# LCEDA_schematic_esp_trans_v2.net
KiCad netlist of a schematic drawn in EasyEDA
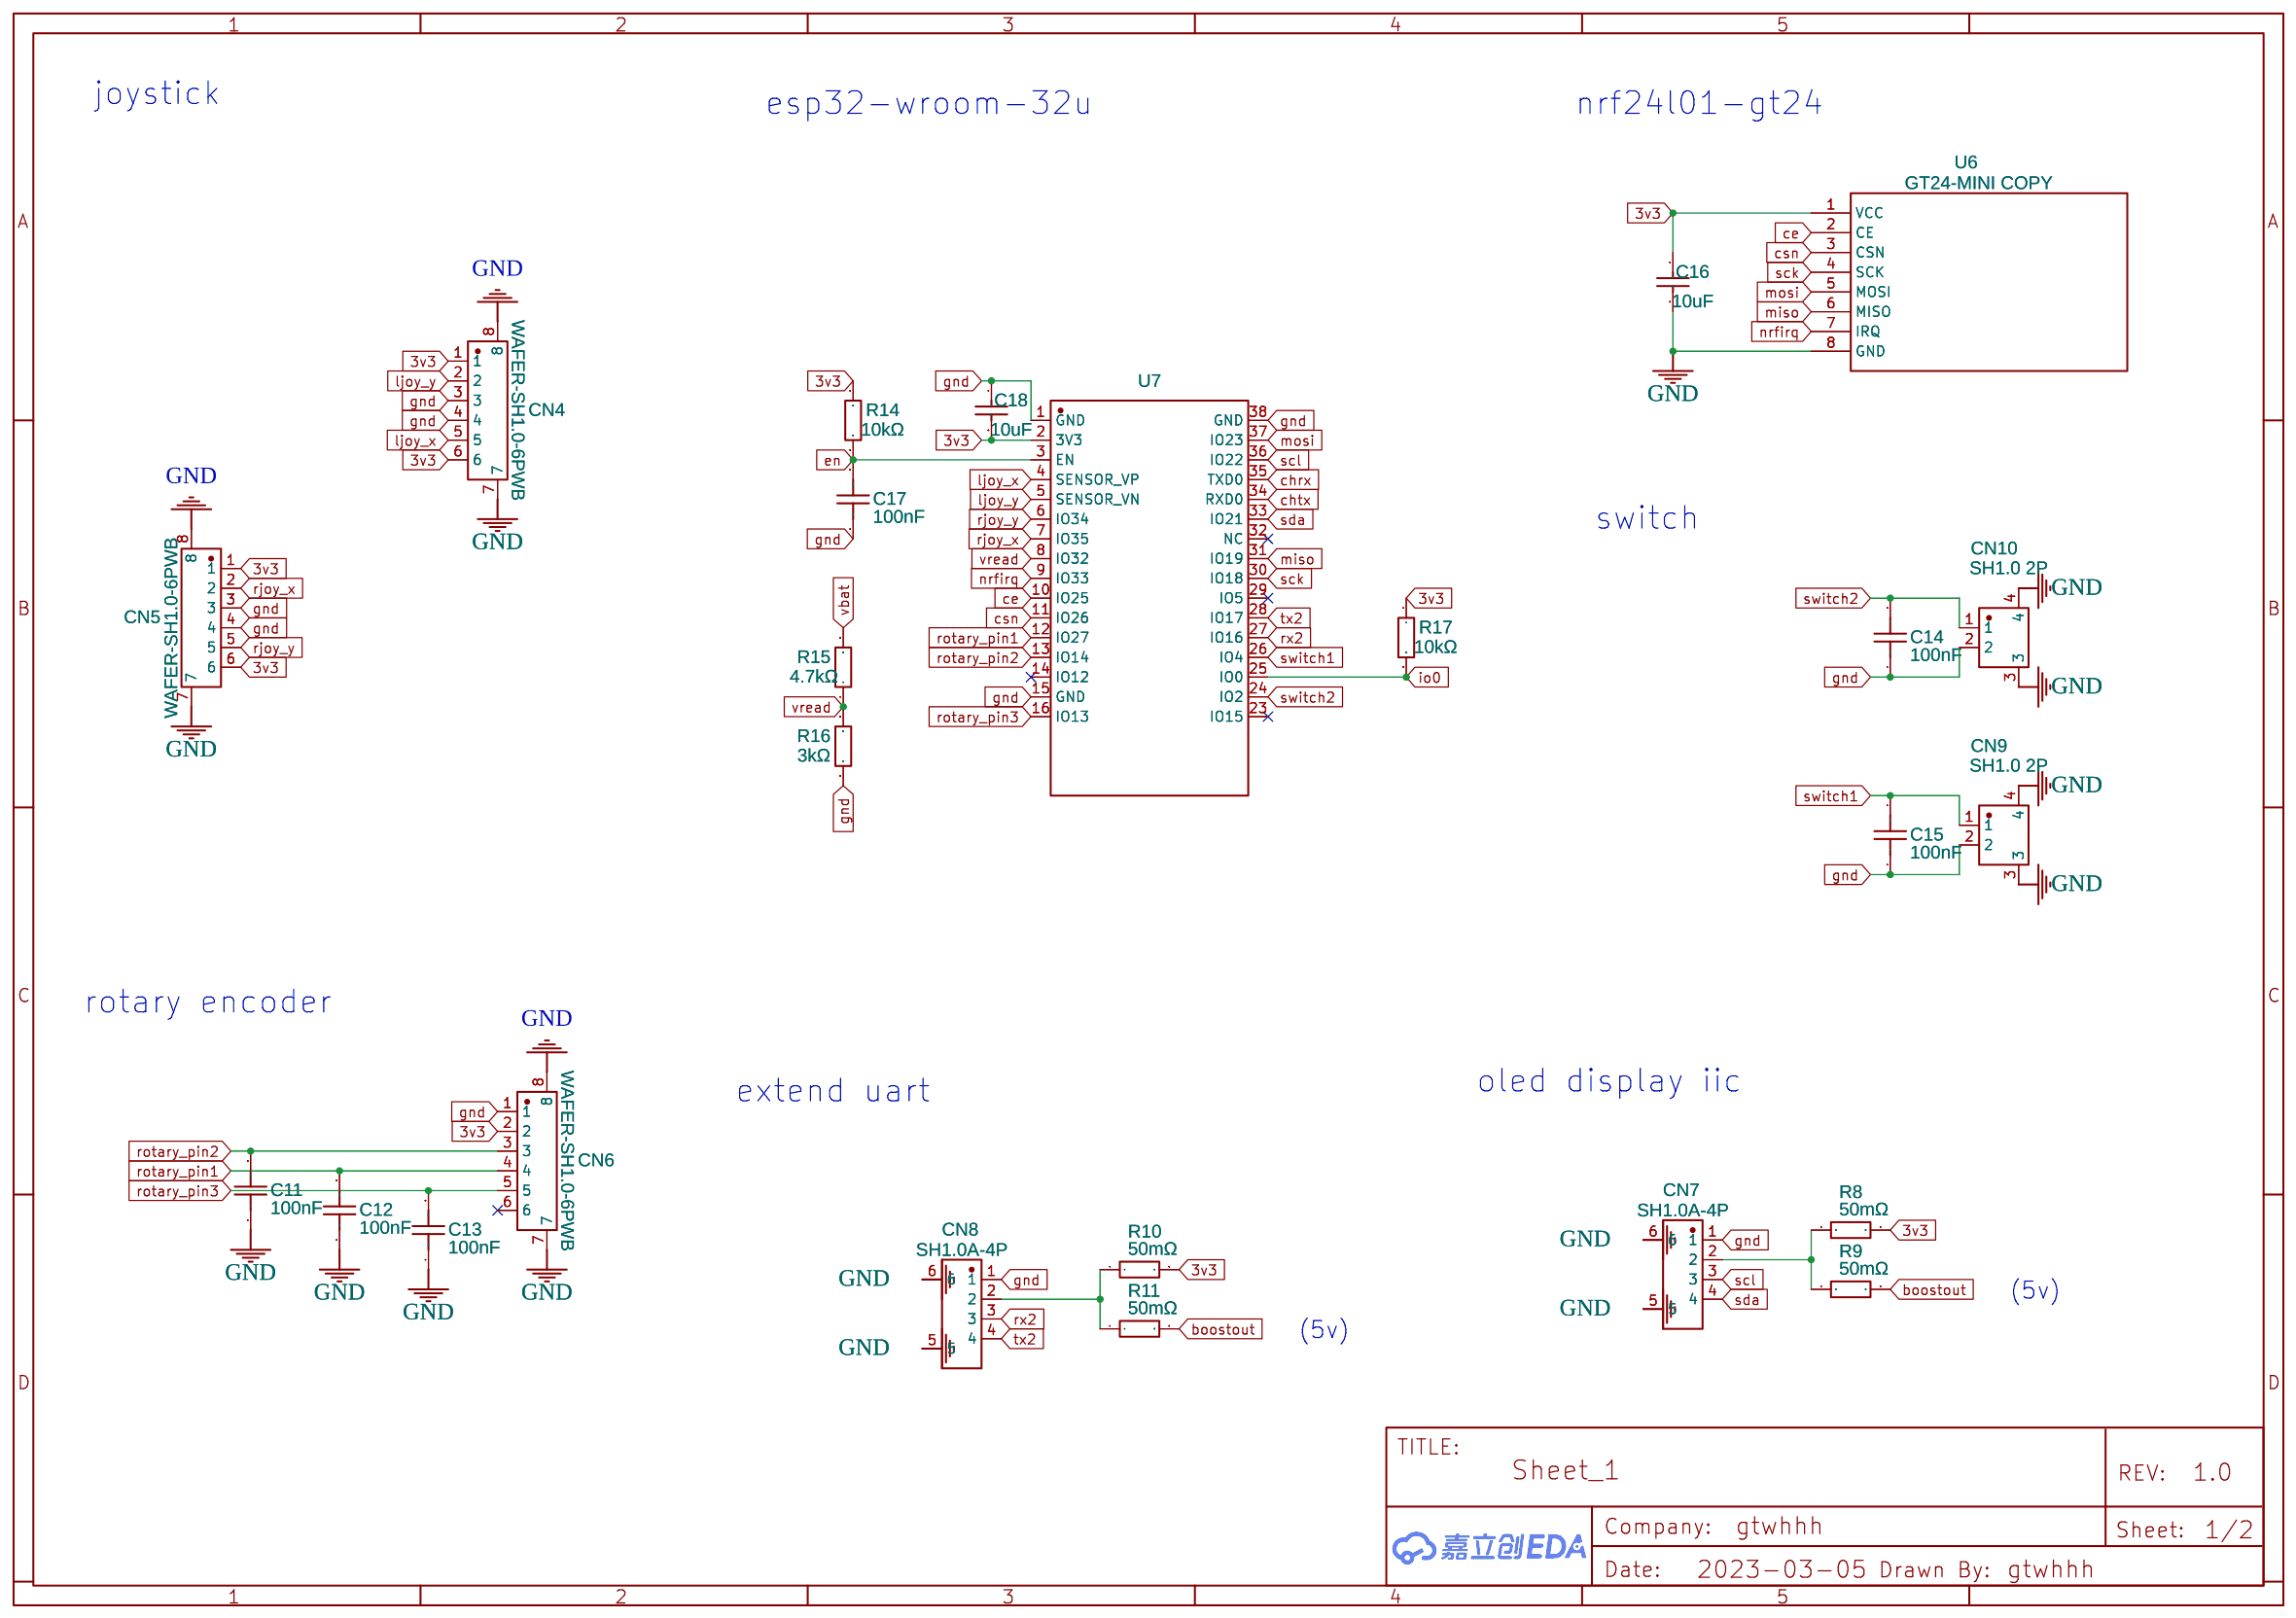
[diagram p0: Sheet_1]
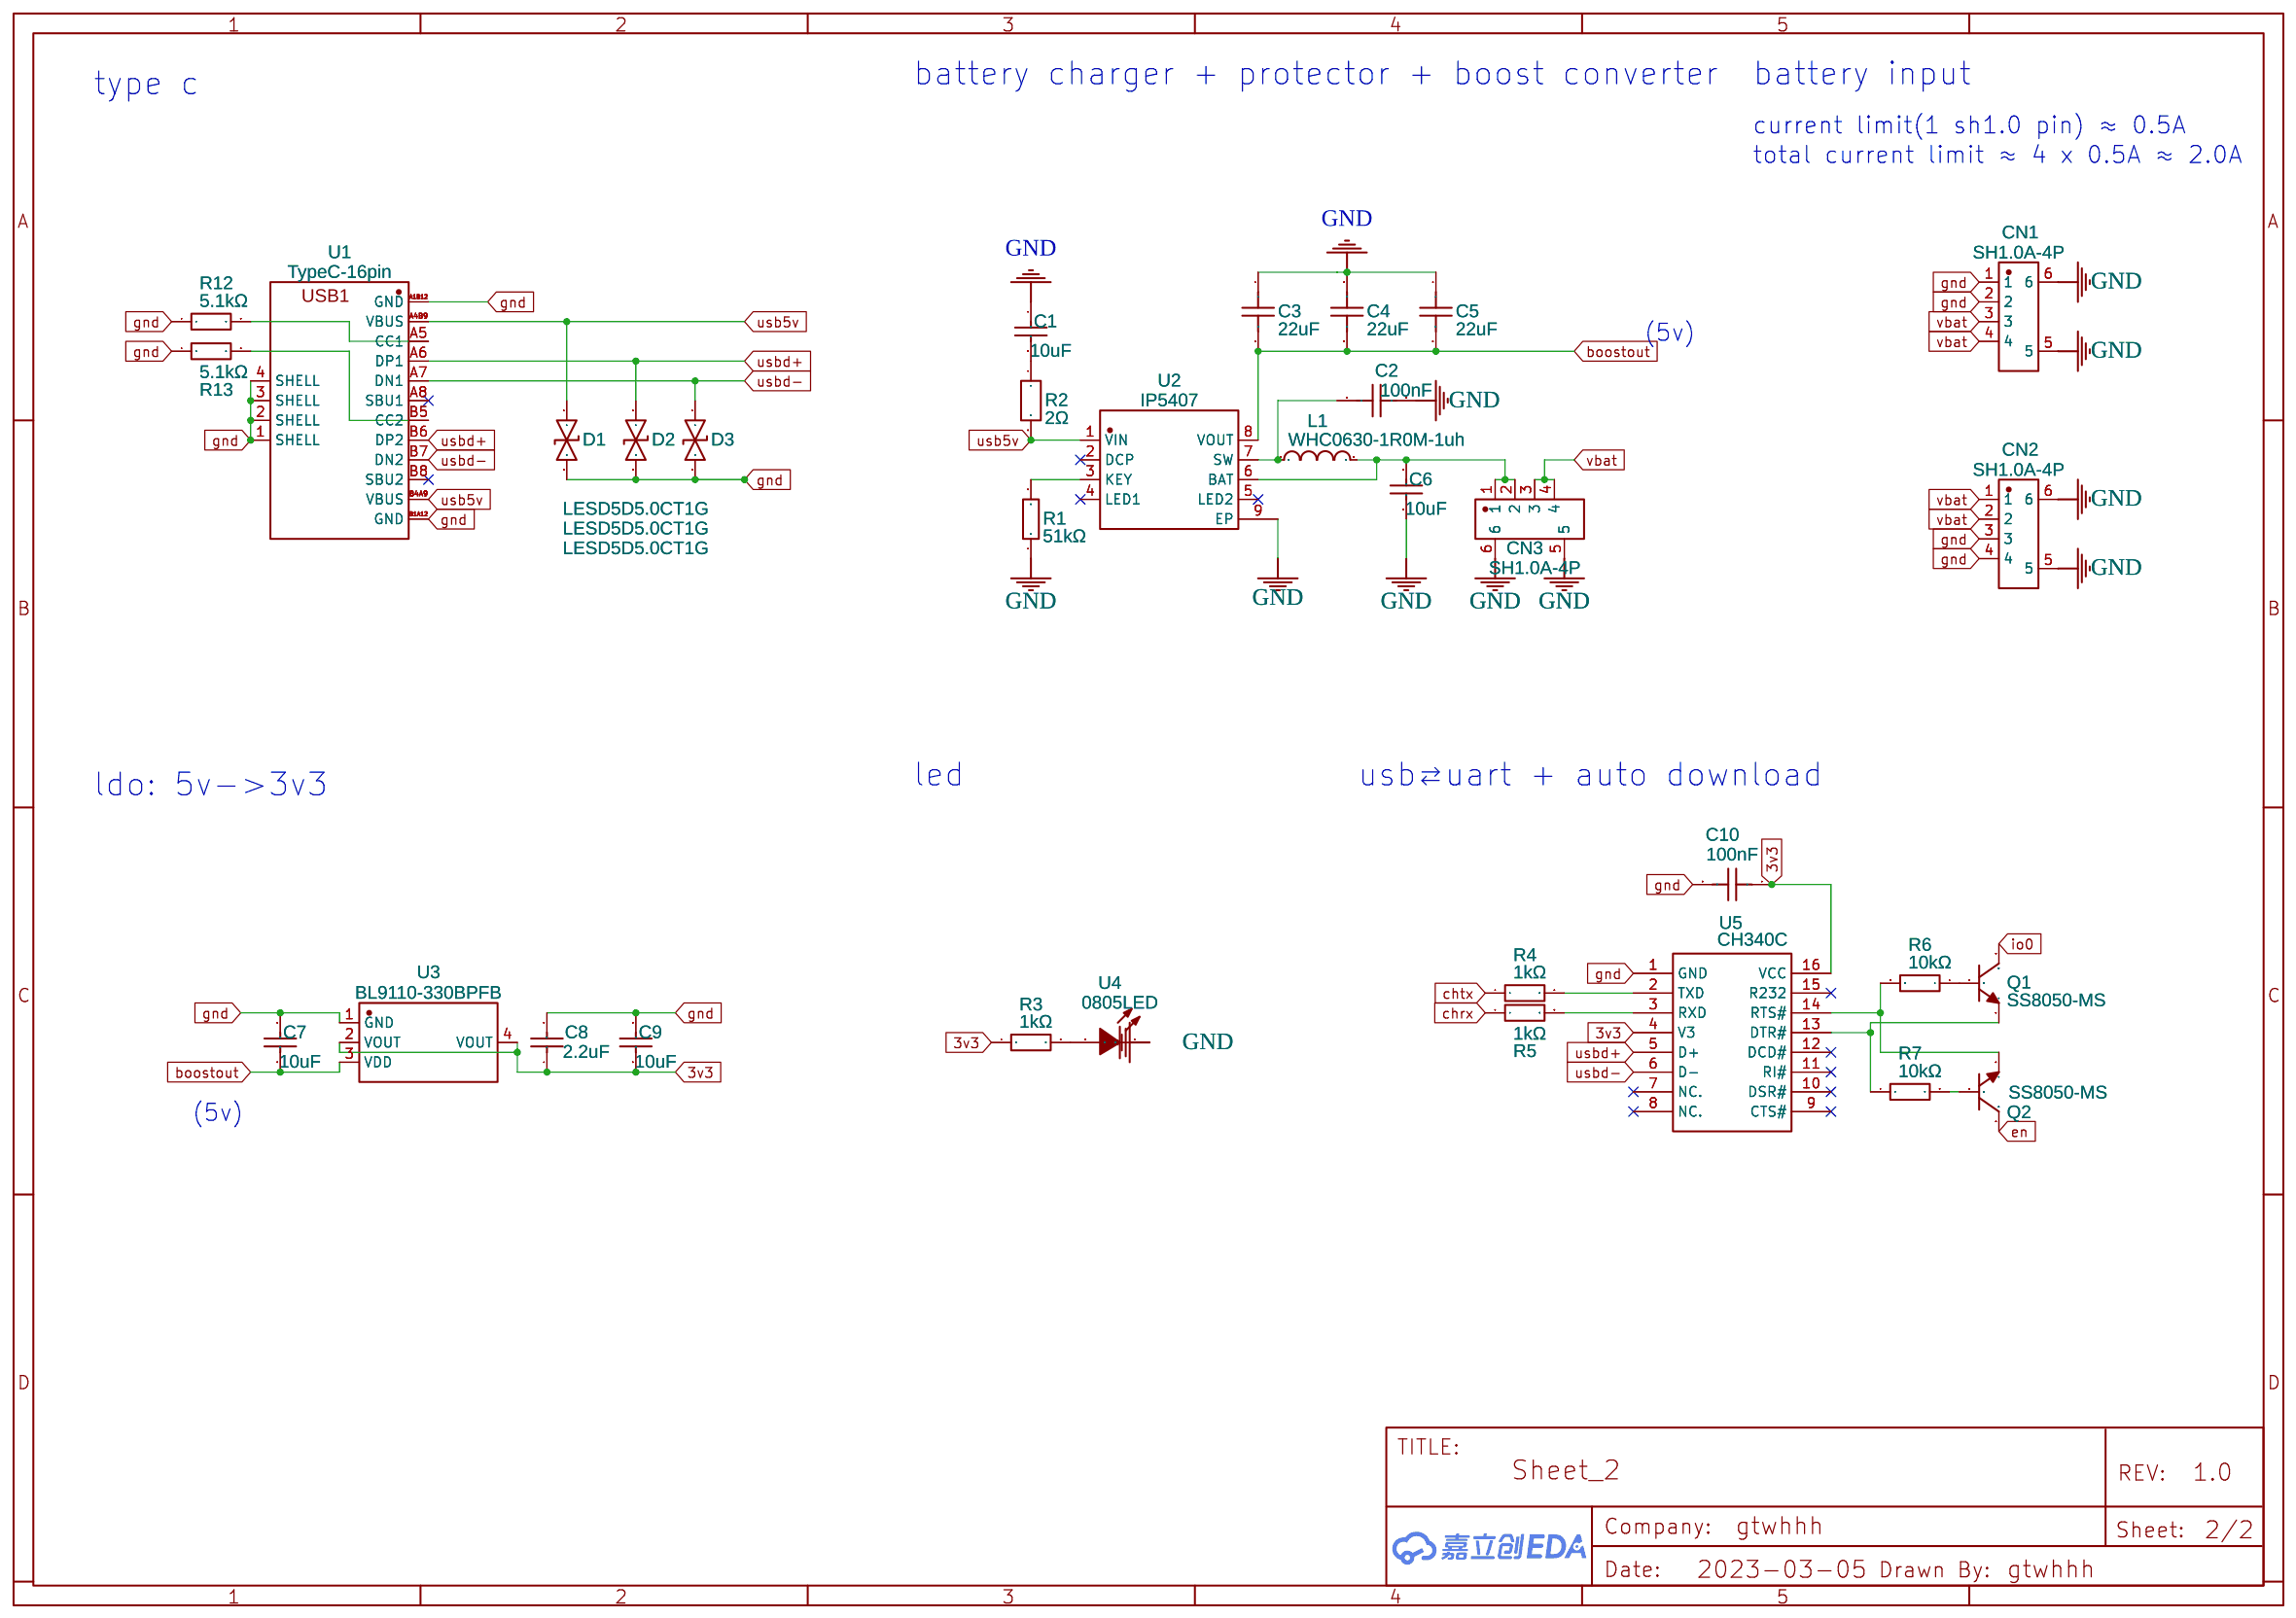
[diagram p1: Sheet_2]

(export (version "E")
  (design (tool "Eeschema 10.0.6"))
  (components
    (comp (ref "C11")
      (value "100nF")
      (fields (field (name "Manufacturer Part") "0805B104K500CT") (field (name "Manufacturer") "Walsin(华新科)"))
      (libsource (lib "") (part "0805B104K500"))
    )
    (comp (ref "C12")
      (value "100nF")
      (fields (field (name "Manufacturer Part") "0805B104K500CT") (field (name "Manufacturer") "Walsin(华新科)"))
      (libsource (lib "") (part "0805B104K500"))
    )
    (comp (ref "C13")
      (value "100nF")
      (fields (field (name "Manufacturer Part") "0805B104K500CT") (field (name "Manufacturer") "Walsin(华新科)"))
      (libsource (lib "") (part "0805B104K500"))
    )
    (comp (ref "C14")
      (value "100nF")
      (fields (field (name "Manufacturer Part") "0805B104K500CT") (field (name "Manufacturer") "Walsin(华新科)"))
      (libsource (lib "") (part "0805B104K500"))
    )
    (comp (ref "C15")
      (value "100nF")
      (fields (field (name "Manufacturer Part") "0805B104K500CT") (field (name "Manufacturer") "Walsin(华新科)"))
      (libsource (lib "") (part "0805B104K500"))
    )
    (comp (ref "C16")
      (value "10uF")
      (fields (field (name "Manufacturer Part") "0805X106K250NT") (field (name "Manufacturer") "FH(风华)"))
      (libsource (lib "") (part "0805X106K250NT"))
    )
    (comp (ref "C17")
      (value "100nF")
      (fields (field (name "Manufacturer Part") "0805B104K500CT") (field (name "Manufacturer") "Walsin(华新科)"))
      (libsource (lib "") (part "0805B104K500"))
    )
    (comp (ref "C18")
      (value "10uF")
      (fields (field (name "Manufacturer Part") "0805X106K250NT") (field (name "Manufacturer") "FH(风华)"))
      (libsource (lib "") (part "0805X106K250NT"))
    )
    (comp (ref "CN4")
      (value "WAFER-SH1.0-6PWB")
      (fields (field (name "Manufacturer") "XUNPU(讯普)"))
      (libsource (lib "") (part "WAFER-SH1.0-6PWB"))
    )
    (comp (ref "CN5")
      (value "WAFER-SH1.0-6PWB")
      (fields (field (name "Manufacturer") "XUNPU(讯普)"))
      (libsource (lib "") (part "WAFER-SH1.0-6PWB_1"))
    )
    (comp (ref "CN6")
      (value "WAFER-SH1.0-6PWB")
      (fields (field (name "Manufacturer") "XUNPU(讯普)"))
      (libsource (lib "") (part "WAFER-SH1.0-6PWB"))
    )
    (comp (ref "CN7")
      (value "SH1.0A-4P")
      (fields (field (name "Manufacturer Part") "SH1.0A-4P 卧贴"))
      (libsource (lib "") (part "SH1.0A-4P 卧贴"))
    )
    (comp (ref "CN8")
      (value "SH1.0A-4P")
      (fields (field (name "Manufacturer Part") "SH1.0A-4P 卧贴"))
      (libsource (lib "") (part "SH1.0A-4P 卧贴"))
    )
    (comp (ref "CN9")
      (value "SH1.0 2P")
      (fields (field (name "Manufacturer Part") "WAFER-SH1.0-2PWB") (field (name "Manufacturer") "XUNPU(讯普)"))
      (libsource (lib "") (part "EPHB_WAFER-SH1.0-2PWB COPY1 SH1.0 2P 卧贴"))
    )
    (comp (ref "CN10")
      (value "SH1.0 2P")
      (fields (field (name "Manufacturer Part") "WAFER-SH1.0-2PWB") (field (name "Manufacturer") "XUNPU(讯普)"))
      (libsource (lib "") (part "EPHB_WAFER-SH1.0-2PWB COPY1 SH1.0 2P 卧贴"))
    )
    (comp (ref "R8")
      (value "50mΩ")
      (fields (field (name "Manufacturer Part") "RL0805FR-070R05L") (field (name "Manufacturer") "YAGEO(国巨)"))
      (libsource (lib "") (part "RL0805FR-070R05L"))
    )
    (comp (ref "R9")
      (value "50mΩ")
      (fields (field (name "Manufacturer Part") "RL0805FR-070R05L") (field (name "Manufacturer") "YAGEO(国巨)"))
      (libsource (lib "") (part "RL0805FR-070R05L"))
    )
    (comp (ref "R10")
      (value "50mΩ")
      (fields (field (name "Manufacturer Part") "RL0805FR-070R05L") (field (name "Manufacturer") "YAGEO(国巨)"))
      (libsource (lib "") (part "RL0805FR-070R05L"))
    )
    (comp (ref "R11")
      (value "50mΩ")
      (fields (field (name "Manufacturer Part") "RL0805FR-070R05L") (field (name "Manufacturer") "YAGEO(国巨)"))
      (libsource (lib "") (part "RL0805FR-070R05L"))
    )
    (comp (ref "R14")
      (value "10kΩ")
      (fields (field (name "Manufacturer Part") "AC0805FR-0710KL") (field (name "Manufacturer") "YAGEO(国巨)"))
      (libsource (lib "") (part "AC0805FR-0710KL"))
    )
    (comp (ref "R15")
      (value "4.7kΩ")
      (fields (field (name "Manufacturer Part") "RC0805JR-074K7L") (field (name "Manufacturer") "YAGEO(国巨)"))
      (libsource (lib "") (part "RC0805JR-074K7L"))
    )
    (comp (ref "R16")
      (value "3kΩ")
      (fields (field (name "Manufacturer Part") "RC0805FR-073KL") (field (name "Manufacturer") "YAGEO(国巨)"))
      (libsource (lib "") (part "RC0805FR-073KL"))
    )
    (comp (ref "R17")
      (value "10kΩ")
      (fields (field (name "Manufacturer Part") "AC0805FR-0710KL") (field (name "Manufacturer") "YAGEO(国巨)"))
      (libsource (lib "") (part "AC0805FR-0710KL"))
    )
    (comp (ref "U6") (value "GT24-MINI COPY") (libsource (lib "") (part "GT24-MINI COPY")))
    (comp (ref "U7")
      (value "NO")
      (fields (field (name "Manufacturer Part") "123"))
      (libsource (lib "") (part "esp3232"))
    )
    (comp (ref "C1")
      (value "10uF")
      (fields (field (name "Manufacturer Part") "0805X106K250NT") (field (name "Manufacturer") "FH(风华)"))
      (libsource (lib "") (part "0805X106K250NT"))
    )
    (comp (ref "C2")
      (value "100nF")
      (fields (field (name "Manufacturer Part") "0805B104K500CT") (field (name "Manufacturer") "Walsin(华新科)"))
      (libsource (lib "") (part "0805B104K500"))
    )
    (comp (ref "C3")
      (value "22uF")
      (fields (field (name "Manufacturer Part") "0805X226M160NT") (field (name "Manufacturer") "FH(风华)"))
      (libsource (lib "") (part "0805X226M160NT"))
    )
    (comp (ref "C4")
      (value "22uF")
      (fields (field (name "Manufacturer Part") "0805X226M160NT") (field (name "Manufacturer") "FH(风华)"))
      (libsource (lib "") (part "0805X226M160NT"))
    )
    (comp (ref "C5")
      (value "22uF")
      (fields (field (name "Manufacturer Part") "0805X226M160NT") (field (name "Manufacturer") "FH(风华)"))
      (libsource (lib "") (part "0805X226M160NT"))
    )
    (comp (ref "C6")
      (value "10uF")
      (fields (field (name "Manufacturer Part") "0805X106K250NT") (field (name "Manufacturer") "FH(风华)"))
      (libsource (lib "") (part "0805X106K250NT"))
    )
    (comp (ref "C7")
      (value "10uF")
      (fields (field (name "Manufacturer Part") "0805X106K250NT") (field (name "Manufacturer") "FH(风华)"))
      (libsource (lib "") (part "0805X106K250NT"))
    )
    (comp (ref "C8")
      (value "2.2uF")
      (fields (field (name "Manufacturer Part") "0805B225K250NT") (field (name "Manufacturer") "FH(风华)"))
      (libsource (lib "") (part "0805B225K250NT"))
    )
    (comp (ref "C9")
      (value "10uF")
      (fields (field (name "Manufacturer Part") "0805X106K250NT") (field (name "Manufacturer") "FH(风华)"))
      (libsource (lib "") (part "0805X106K250NT"))
    )
    (comp (ref "C10")
      (value "100nF")
      (fields (field (name "Manufacturer Part") "0805B104K500CT") (field (name "Manufacturer") "Walsin(华新科)"))
      (libsource (lib "") (part "0805B104K500"))
    )
    (comp (ref "CN1")
      (value "SH1.0A-4P")
      (fields (field (name "Manufacturer Part") "SH1.0A-4P 卧贴"))
      (libsource (lib "") (part "SH1.0A-4P 卧贴_1"))
    )
    (comp (ref "CN2")
      (value "SH1.0A-4P")
      (fields (field (name "Manufacturer Part") "SH1.0A-4P 卧贴"))
      (libsource (lib "") (part "SH1.0A-4P 卧贴_1"))
    )
    (comp (ref "CN3")
      (value "SH1.0A-4P")
      (fields (field (name "Manufacturer Part") "SH1.0A-4P 卧贴"))
      (libsource (lib "") (part "SH1.0A-4P 卧贴"))
    )
    (comp (ref "D1")
      (value "LESD5D5.0CT1G")
      (fields (field (name "Manufacturer") "LRC(乐山无线电)"))
      (libsource (lib "") (part "LESD5D5.0CT1G"))
    )
    (comp (ref "D2")
      (value "LESD5D5.0CT1G")
      (fields (field (name "Manufacturer") "LRC(乐山无线电)"))
      (libsource (lib "") (part "LESD5D5.0CT1G"))
    )
    (comp (ref "D3")
      (value "LESD5D5.0CT1G")
      (fields (field (name "Manufacturer") "LRC(乐山无线电)"))
      (libsource (lib "") (part "LESD5D5.0CT1G"))
    )
    (comp (ref "L1")
      (value "WHC0630-1R0M-1uh")
      (fields (field (name "Manufacturer Part") "MPCA-0630-1R0-M") (field (name "Manufacturer") "MAZO"))
      (libsource (lib "") (part "0630-1R0电感"))
    )
    (comp (ref "Q1")
      (value "SS8050-MS")
      (fields (field (name "Manufacturer") "MSKSEMI(美森科)"))
      (libsource (lib "") (part "SS8050-MS_1"))
    )
    (comp (ref "Q2")
      (value "SS8050-MS")
      (fields (field (name "Manufacturer") "MSKSEMI(美森科)"))
      (libsource (lib "") (part "SS8050-MS"))
    )
    (comp (ref "R1")
      (value "51kΩ")
      (fields (field (name "Manufacturer Part") "RC0805FR-0751KL") (field (name "Manufacturer") "YAGEO(国巨)"))
      (libsource (lib "") (part "RC0805FR-0751KL"))
    )
    (comp (ref "R2")
      (value "2Ω")
      (fields (field (name "Manufacturer Part") "RT0805BRD072RL") (field (name "Manufacturer") "YAGEO(国巨)"))
      (libsource (lib "") (part "RT0805BRD072RL"))
    )
    (comp (ref "R3")
      (value "1kΩ")
      (fields (field (name "Manufacturer Part") "RC0805FR-071KL") (field (name "Manufacturer") "YAGEO(国巨)"))
      (libsource (lib "") (part "RC0805FR-071KL"))
    )
    (comp (ref "R4")
      (value "1kΩ")
      (fields (field (name "Manufacturer Part") "RC0805FR-071KL") (field (name "Manufacturer") "YAGEO(国巨)"))
      (libsource (lib "") (part "RC0805FR-071KL"))
    )
    (comp (ref "R5")
      (value "1kΩ")
      (fields (field (name "Manufacturer Part") "RC0805FR-071KL") (field (name "Manufacturer") "YAGEO(国巨)"))
      (libsource (lib "") (part "RC0805FR-071KL"))
    )
    (comp (ref "R6")
      (value "10kΩ")
      (fields (field (name "Manufacturer Part") "AC0805FR-0710KL") (field (name "Manufacturer") "YAGEO(国巨)"))
      (libsource (lib "") (part "AC0805FR-0710KL_1"))
    )
    (comp (ref "R7")
      (value "10kΩ")
      (fields (field (name "Manufacturer Part") "AC0805FR-0710KL") (field (name "Manufacturer") "YAGEO(国巨)"))
      (libsource (lib "") (part "AC0805FR-0710KL"))
    )
    (comp (ref "R12")
      (value "5.1kΩ")
      (fields (field (name "Manufacturer Part") "AC0805FR-075K1L") (field (name "Manufacturer") "YAGEO(国巨)"))
      (libsource (lib "") (part "AC0805FR-075K1L"))
    )
    (comp (ref "R13")
      (value "5.1kΩ")
      (fields (field (name "Manufacturer Part") "AC0805FR-075K1L") (field (name "Manufacturer") "YAGEO(国巨)"))
      (libsource (lib "") (part "AC0805FR-075K1L"))
    )
    (comp (ref "U1") (value "TypeC-16pin") (libsource (lib "") (part "TypeC-16pin")))
    (comp (ref "U2") (value "IP5407") (libsource (lib "") (part "IP5407")))
    (comp (ref "U3")
      (value "BL9110-330BPFB")
      (fields (field (name "Manufacturer") "BL(上海贝岭)"))
      (libsource (lib "") (part "BL9110-330BPFB"))
    )
    (comp (ref "U4")
      (value "0805LED")
      (fields (field (name "Manufacturer Part") "白光0805LED"))
      (libsource (lib "") (part "白光0805LED"))
    )
    (comp (ref "U5")
      (value "CH340C")
      (fields (field (name "Manufacturer") "WCH(南京沁恒)"))
      (libsource (lib "") (part "CH340C"))
    )
  )
  (nets
    (net (code "1") (name "3v3") (class "Default")
      (node (ref "C10") (pin "1") (pinfunction "1_1") (pintype "unspecified"))
      (node (ref "C16") (pin "1") (pinfunction "1_1") (pintype "input"))
      (node (ref "C18") (pin "2") (pinfunction "2_2") (pintype "input"))
      (node (ref "C8") (pin "1") (pinfunction "1_1") (pintype "input"))
      (node (ref "C9") (pin "2") (pinfunction "2_2") (pintype "input"))
      (node (ref "CN4") (pin "1") (pinfunction "1_1") (pintype "unspecified"))
      (node (ref "CN4") (pin "6") (pinfunction "6_6") (pintype "unspecified"))
      (node (ref "CN5") (pin "1") (pinfunction "1_1") (pintype "unspecified"))
      (node (ref "CN5") (pin "6") (pinfunction "6_6") (pintype "unspecified"))
      (node (ref "CN6") (pin "2") (pinfunction "2_2") (pintype "unspecified"))
      (node (ref "R10") (pin "2") (pinfunction "2_2") (pintype "unspecified"))
      (node (ref "R14") (pin "1") (pinfunction "1_1") (pintype "input"))
      (node (ref "R17") (pin "1") (pinfunction "1_1") (pintype "input"))
      (node (ref "R3") (pin "1") (pinfunction "1_1") (pintype "input"))
      (node (ref "R8") (pin "2") (pinfunction "2_2") (pintype "unspecified"))
      (node (ref "U3") (pin "2") (pinfunction "VOUT_2") (pintype "unspecified"))
      (node (ref "U3") (pin "4") (pinfunction "VOUT_4") (pintype "unspecified"))
      (node (ref "U5") (pin "16") (pinfunction "VCC_16") (pintype "unspecified"))
      (node (ref "U5") (pin "4") (pinfunction "V3_4") (pintype "unspecified"))
      (node (ref "U6") (pin "1") (pinfunction "VCC_1") (pintype "unspecified"))
      (node (ref "U7") (pin "2") (pinfunction "3V3_2") (pintype "unspecified"))
    )
    (net (code "2") (name "GND") (class "Default")
      (node (ref "C1") (pin "1") (pinfunction "1_1") (pintype "input"))
      (node (ref "C11") (pin "1") (pinfunction "1_1") (pintype "unspecified"))
      (node (ref "C12") (pin "1") (pinfunction "1_1") (pintype "unspecified"))
      (node (ref "C13") (pin "1") (pinfunction "1_1") (pintype "unspecified"))
      (node (ref "C16") (pin "2") (pinfunction "2_2") (pintype "input"))
      (node (ref "C2") (pin "1") (pinfunction "1_1") (pintype "unspecified"))
      (node (ref "C3") (pin "1") (pinfunction "1_1") (pintype "unspecified"))
      (node (ref "C4") (pin "1") (pinfunction "1_1") (pintype "unspecified"))
      (node (ref "C5") (pin "1") (pinfunction "1_1") (pintype "unspecified"))
      (node (ref "C6") (pin "2") (pinfunction "2_2") (pintype "input"))
      (node (ref "CN1") (pin "5") (pinfunction "5_5") (pintype "unspecified"))
      (node (ref "CN1") (pin "6") (pinfunction "6_6") (pintype "unspecified"))
      (node (ref "CN10") (pin "3") (pinfunction "3_3") (pintype "unspecified"))
      (node (ref "CN10") (pin "4") (pinfunction "4_4") (pintype "unspecified"))
      (node (ref "CN2") (pin "5") (pinfunction "5_5") (pintype "unspecified"))
      (node (ref "CN2") (pin "6") (pinfunction "6_6") (pintype "unspecified"))
      (node (ref "CN3") (pin "5") (pinfunction "5_5") (pintype "unspecified"))
      (node (ref "CN3") (pin "6") (pinfunction "6_6") (pintype "unspecified"))
      (node (ref "CN4") (pin "7") (pinfunction "7_7") (pintype "unspecified"))
      (node (ref "CN4") (pin "8") (pinfunction "8_8") (pintype "unspecified"))
      (node (ref "CN5") (pin "7") (pinfunction "7_7") (pintype "unspecified"))
      (node (ref "CN5") (pin "8") (pinfunction "8_8") (pintype "unspecified"))
      (node (ref "CN6") (pin "7") (pinfunction "7_7") (pintype "unspecified"))
      (node (ref "CN6") (pin "8") (pinfunction "8_8") (pintype "unspecified"))
      (node (ref "CN7") (pin "5") (pinfunction "5_5") (pintype "unspecified"))
      (node (ref "CN7") (pin "6") (pinfunction "6_6") (pintype "unspecified"))
      (node (ref "CN8") (pin "5") (pinfunction "5_5") (pintype "unspecified"))
      (node (ref "CN8") (pin "6") (pinfunction "6_6") (pintype "unspecified"))
      (node (ref "CN9") (pin "3") (pinfunction "3_3") (pintype "unspecified"))
      (node (ref "CN9") (pin "4") (pinfunction "4_4") (pintype "unspecified"))
      (node (ref "R1") (pin "1") (pinfunction "1_1") (pintype "input"))
      (node (ref "U2") (pin "9") (pinfunction "EP_9") (pintype "unspecified"))
      (node (ref "U4") (pin "1") (pinfunction "C_1") (pintype "unspecified"))
      (node (ref "U6") (pin "8") (pinfunction "GND_8") (pintype "unspecified"))
    )
    (net (code "3") (name "Net-(C1-Pad2)") (class "Default")
      (node (ref "C1") (pin "2") (pinfunction "2_2") (pintype "input"))
      (node (ref "R2") (pin "1") (pinfunction "1_1") (pintype "unspecified"))
    )
    (net (code "4") (name "Net-(CN7-Pad2)") (class "Default")
      (node (ref "CN7") (pin "2") (pinfunction "2_2") (pintype "unspecified"))
      (node (ref "R8") (pin "1") (pinfunction "1_1") (pintype "unspecified"))
      (node (ref "R9") (pin "1") (pinfunction "1_1") (pintype "unspecified"))
    )
    (net (code "5") (name "Net-(CN8-Pad2)") (class "Default")
      (node (ref "CN8") (pin "2") (pinfunction "2_2") (pintype "unspecified"))
      (node (ref "R10") (pin "1") (pinfunction "1_1") (pintype "unspecified"))
      (node (ref "R11") (pin "1") (pinfunction "1_1") (pintype "unspecified"))
    )
    (net (code "6") (name "Net-(Q1-B)") (class "Default")
      (node (ref "Q1") (pin "1") (pinfunction "B_1") (pintype "input"))
      (node (ref "R6") (pin "1") (pinfunction "1_1") (pintype "input"))
    )
    (net (code "7") (name "Net-(Q1-E)") (class "Default")
      (node (ref "Q1") (pin "2") (pinfunction "E_2") (pintype "input"))
      (node (ref "R7") (pin "1") (pinfunction "1_1") (pintype "input"))
      (node (ref "U5") (pin "13") (pinfunction "DTR#_13") (pintype "unspecified"))
    )
    (net (code "8") (name "Net-(Q2-B)") (class "Default")
      (node (ref "Q2") (pin "1") (pinfunction "B_1") (pintype "input"))
      (node (ref "R7") (pin "2") (pinfunction "2_2") (pintype "input"))
    )
    (net (code "9") (name "Net-(Q2-E)") (class "Default")
      (node (ref "Q2") (pin "2") (pinfunction "E_2") (pintype "input"))
      (node (ref "R6") (pin "2") (pinfunction "2_2") (pintype "input"))
      (node (ref "U5") (pin "14") (pinfunction "RTS#_14") (pintype "unspecified"))
    )
    (net (code "10") (name "Net-(U1-CC1)") (class "Default")
      (node (ref "R12") (pin "2") (pinfunction "2_2") (pintype "unspecified"))
      (node (ref "U1") (pin "A5") (pinfunction "CC1_A5") (pintype "unspecified"))
    )
    (net (code "11") (name "Net-(U1-CC2)") (class "Default")
      (node (ref "R13") (pin "2") (pinfunction "2_2") (pintype "unspecified"))
      (node (ref "U1") (pin "B5") (pinfunction "CC2_B5") (pintype "unspecified"))
    )
    (net (code "12") (name "Net-(U2-BAT)") (class "Default")
      (node (ref "C6") (pin "1") (pinfunction "1_1") (pintype "input"))
      (node (ref "CN3") (pin "1") (pinfunction "1_1") (pintype "unspecified"))
      (node (ref "CN3") (pin "2") (pinfunction "2_2") (pintype "unspecified"))
      (node (ref "L1") (pin "2") (pinfunction "2_2") (pintype "unspecified"))
      (node (ref "U2") (pin "6") (pinfunction "BAT_6") (pintype "unspecified"))
    )
    (net (code "13") (name "Net-(U2-KEY)") (class "Default")
      (node (ref "R1") (pin "2") (pinfunction "2_2") (pintype "input"))
      (node (ref "U2") (pin "3") (pinfunction "KEY_3") (pintype "unspecified"))
    )
    (net (code "14") (name "Net-(U2-SW)") (class "Default")
      (node (ref "C2") (pin "2") (pinfunction "2_2") (pintype "unspecified"))
      (node (ref "L1") (pin "1") (pinfunction "1_1") (pintype "unspecified"))
      (node (ref "U2") (pin "7") (pinfunction "SW_7") (pintype "unspecified"))
    )
    (net (code "15") (name "Net-(U4-A)") (class "Default")
      (node (ref "R3") (pin "2") (pinfunction "2_2") (pintype "input"))
      (node (ref "U4") (pin "2") (pinfunction "A_2") (pintype "unspecified"))
    )
    (net (code "16") (name "Net-(U5-RXD)") (class "Default")
      (node (ref "R5") (pin "2") (pinfunction "2_2") (pintype "input"))
      (node (ref "U5") (pin "3") (pinfunction "RXD_3") (pintype "unspecified"))
    )
    (net (code "17") (name "Net-(U5-TXD)") (class "Default")
      (node (ref "R4") (pin "2") (pinfunction "2_2") (pintype "input"))
      (node (ref "U5") (pin "2") (pinfunction "TXD_2") (pintype "unspecified"))
    )
    (net (code "18") (name "boostout") (class "Default")
      (node (ref "C3") (pin "2") (pinfunction "2_2") (pintype "unspecified"))
      (node (ref "C4") (pin "2") (pinfunction "2_2") (pintype "unspecified"))
      (node (ref "C5") (pin "2") (pinfunction "2_2") (pintype "unspecified"))
      (node (ref "C7") (pin "2") (pinfunction "2_2") (pintype "input"))
      (node (ref "R11") (pin "2") (pinfunction "2_2") (pintype "unspecified"))
      (node (ref "R9") (pin "2") (pinfunction "2_2") (pintype "unspecified"))
      (node (ref "U2") (pin "8") (pinfunction "VOUT_8") (pintype "unspecified"))
      (node (ref "U3") (pin "3") (pinfunction "VDD_3") (pintype "unspecified"))
    )
    (net (code "19") (name "ce") (class "Default")
      (node (ref "U6") (pin "2") (pinfunction "CE_2") (pintype "unspecified"))
      (node (ref "U7") (pin "10") (pinfunction "IO25_10") (pintype "unspecified"))
    )
    (net (code "20") (name "chrx") (class "Default")
      (node (ref "R5") (pin "1") (pinfunction "1_1") (pintype "input"))
      (node (ref "U7") (pin "35") (pinfunction "TXD0_35") (pintype "unspecified"))
    )
    (net (code "21") (name "chtx") (class "Default")
      (node (ref "R4") (pin "1") (pinfunction "1_1") (pintype "input"))
      (node (ref "U7") (pin "34") (pinfunction "RXD0_34") (pintype "unspecified"))
    )
    (net (code "22") (name "csn") (class "Default")
      (node (ref "U6") (pin "3") (pinfunction "CSN_3") (pintype "unspecified"))
      (node (ref "U7") (pin "11") (pinfunction "IO26_11") (pintype "unspecified"))
    )
    (net (code "23") (name "en") (class "Default")
      (node (ref "C17") (pin "2") (pinfunction "2_2") (pintype "unspecified"))
      (node (ref "Q2") (pin "3") (pinfunction "C_3") (pintype "input"))
      (node (ref "R14") (pin "2") (pinfunction "2_2") (pintype "input"))
      (node (ref "U7") (pin "3") (pinfunction "EN_3") (pintype "unspecified"))
    )
    (net (code "24") (name "gnd") (class "Default")
      (node (ref "C10") (pin "2") (pinfunction "2_2") (pintype "unspecified"))
      (node (ref "C14") (pin "1") (pinfunction "1_1") (pintype "unspecified"))
      (node (ref "C15") (pin "1") (pinfunction "1_1") (pintype "unspecified"))
      (node (ref "C17") (pin "1") (pinfunction "1_1") (pintype "unspecified"))
      (node (ref "C18") (pin "1") (pinfunction "1_1") (pintype "input"))
      (node (ref "C7") (pin "1") (pinfunction "1_1") (pintype "input"))
      (node (ref "C8") (pin "2") (pinfunction "2_2") (pintype "input"))
      (node (ref "C9") (pin "1") (pinfunction "1_1") (pintype "input"))
      (node (ref "CN1") (pin "1") (pinfunction "1_1") (pintype "unspecified"))
      (node (ref "CN1") (pin "2") (pinfunction "2_2") (pintype "unspecified"))
      (node (ref "CN10") (pin "2") (pinfunction "2_2") (pintype "unspecified"))
      (node (ref "CN2") (pin "3") (pinfunction "3_3") (pintype "unspecified"))
      (node (ref "CN2") (pin "4") (pinfunction "4_4") (pintype "unspecified"))
      (node (ref "CN4") (pin "3") (pinfunction "3_3") (pintype "unspecified"))
      (node (ref "CN4") (pin "4") (pinfunction "4_4") (pintype "unspecified"))
      (node (ref "CN5") (pin "3") (pinfunction "3_3") (pintype "unspecified"))
      (node (ref "CN5") (pin "4") (pinfunction "4_4") (pintype "unspecified"))
      (node (ref "CN6") (pin "1") (pinfunction "1_1") (pintype "unspecified"))
      (node (ref "CN7") (pin "1") (pinfunction "1_1") (pintype "unspecified"))
      (node (ref "CN8") (pin "1") (pinfunction "1_1") (pintype "unspecified"))
      (node (ref "CN9") (pin "2") (pinfunction "2_2") (pintype "unspecified"))
      (node (ref "D1") (pin "2") (pinfunction "2_2") (pintype "unspecified"))
      (node (ref "D2") (pin "2") (pinfunction "2_2") (pintype "unspecified"))
      (node (ref "D3") (pin "2") (pinfunction "2_2") (pintype "unspecified"))
      (node (ref "R12") (pin "1") (pinfunction "1_1") (pintype "unspecified"))
      (node (ref "R13") (pin "1") (pinfunction "1_1") (pintype "unspecified"))
      (node (ref "R16") (pin "1") (pinfunction "1_1") (pintype "input"))
      (node (ref "U1") (pin "1") (pinfunction "SHELL_1") (pintype "unspecified"))
      (node (ref "U1") (pin "2") (pinfunction "SHELL_2") (pintype "unspecified"))
      (node (ref "U1") (pin "3") (pinfunction "SHELL_3") (pintype "unspecified"))
      (node (ref "U1") (pin "4") (pinfunction "SHELL_4") (pintype "unspecified"))
      (node (ref "U1") (pin "A1B12") (pinfunction "GND_A1B12") (pintype "unspecified"))
      (node (ref "U1") (pin "B1A12") (pinfunction "GND_B1A12") (pintype "unspecified"))
      (node (ref "U3") (pin "1") (pinfunction "GND_1") (pintype "unspecified"))
      (node (ref "U5") (pin "1") (pinfunction "GND_1") (pintype "unspecified"))
      (node (ref "U7") (pin "1") (pinfunction "GND_1") (pintype "unspecified"))
      (node (ref "U7") (pin "15") (pinfunction "GND_15") (pintype "unspecified"))
      (node (ref "U7") (pin "38") (pinfunction "GND_38") (pintype "unspecified"))
    )
    (net (code "25") (name "io0") (class "Default")
      (node (ref "Q1") (pin "3") (pinfunction "C_3") (pintype "input"))
      (node (ref "R17") (pin "2") (pinfunction "2_2") (pintype "input"))
      (node (ref "U7") (pin "25") (pinfunction "IO0_25") (pintype "unspecified"))
    )
    (net (code "26") (name "ljoy_x") (class "Default")
      (node (ref "CN4") (pin "5") (pinfunction "5_5") (pintype "unspecified"))
      (node (ref "U7") (pin "4") (pinfunction "SENSOR_VP_4") (pintype "unspecified"))
    )
    (net (code "27") (name "ljoy_y") (class "Default")
      (node (ref "CN4") (pin "2") (pinfunction "2_2") (pintype "unspecified"))
      (node (ref "U7") (pin "5") (pinfunction "SENSOR_VN_5") (pintype "unspecified"))
    )
    (net (code "28") (name "miso") (class "Default")
      (node (ref "U6") (pin "6") (pinfunction "MISO_6") (pintype "unspecified"))
      (node (ref "U7") (pin "31") (pinfunction "IO19_31") (pintype "unspecified"))
    )
    (net (code "29") (name "mosi") (class "Default")
      (node (ref "U6") (pin "5") (pinfunction "MOSI_5") (pintype "unspecified"))
      (node (ref "U7") (pin "37") (pinfunction "IO23_37") (pintype "unspecified"))
    )
    (net (code "30") (name "nrfirq") (class "Default")
      (node (ref "U6") (pin "7") (pinfunction "IRQ_7") (pintype "unspecified"))
      (node (ref "U7") (pin "9") (pinfunction "IO33_9") (pintype "unspecified"))
    )
    (net (code "31") (name "rjoy_x") (class "Default")
      (node (ref "CN5") (pin "2") (pinfunction "2_2") (pintype "unspecified"))
      (node (ref "U7") (pin "7") (pinfunction "IO35_7") (pintype "unspecified"))
    )
    (net (code "32") (name "rjoy_y") (class "Default")
      (node (ref "CN5") (pin "5") (pinfunction "5_5") (pintype "unspecified"))
      (node (ref "U7") (pin "6") (pinfunction "IO34_6") (pintype "unspecified"))
    )
    (net (code "33") (name "rotary_pin1") (class "Default")
      (node (ref "C12") (pin "2") (pinfunction "2_2") (pintype "unspecified"))
      (node (ref "CN6") (pin "4") (pinfunction "4_4") (pintype "unspecified"))
      (node (ref "U7") (pin "12") (pinfunction "IO27_12") (pintype "unspecified"))
    )
    (net (code "34") (name "rotary_pin2") (class "Default")
      (node (ref "C11") (pin "2") (pinfunction "2_2") (pintype "unspecified"))
      (node (ref "CN6") (pin "3") (pinfunction "3_3") (pintype "unspecified"))
      (node (ref "U7") (pin "13") (pinfunction "IO14_13") (pintype "unspecified"))
    )
    (net (code "35") (name "rotary_pin3") (class "Default")
      (node (ref "C13") (pin "2") (pinfunction "2_2") (pintype "unspecified"))
      (node (ref "CN6") (pin "5") (pinfunction "5_5") (pintype "unspecified"))
      (node (ref "U7") (pin "16") (pinfunction "IO13_16") (pintype "unspecified"))
    )
    (net (code "36") (name "rx2") (class "Default")
      (node (ref "CN8") (pin "3") (pinfunction "3_3") (pintype "unspecified"))
      (node (ref "U7") (pin "27") (pinfunction "IO16_27") (pintype "unspecified"))
    )
    (net (code "37") (name "sck") (class "Default")
      (node (ref "U6") (pin "4") (pinfunction "SCK_4") (pintype "unspecified"))
      (node (ref "U7") (pin "30") (pinfunction "IO18_30") (pintype "unspecified"))
    )
    (net (code "38") (name "scl") (class "Default")
      (node (ref "CN7") (pin "3") (pinfunction "3_3") (pintype "unspecified"))
      (node (ref "U7") (pin "36") (pinfunction "IO22_36") (pintype "unspecified"))
    )
    (net (code "39") (name "sda") (class "Default")
      (node (ref "CN7") (pin "4") (pinfunction "4_4") (pintype "unspecified"))
      (node (ref "U7") (pin "33") (pinfunction "IO21_33") (pintype "unspecified"))
    )
    (net (code "40") (name "switch1") (class "Default")
      (node (ref "C15") (pin "2") (pinfunction "2_2") (pintype "unspecified"))
      (node (ref "CN9") (pin "1") (pinfunction "1_1") (pintype "unspecified"))
      (node (ref "U7") (pin "26") (pinfunction "IO4_26") (pintype "unspecified"))
    )
    (net (code "41") (name "switch2") (class "Default")
      (node (ref "C14") (pin "2") (pinfunction "2_2") (pintype "unspecified"))
      (node (ref "CN10") (pin "1") (pinfunction "1_1") (pintype "unspecified"))
      (node (ref "U7") (pin "24") (pinfunction "IO2_24") (pintype "unspecified"))
    )
    (net (code "42") (name "tx2") (class "Default")
      (node (ref "CN8") (pin "4") (pinfunction "4_4") (pintype "unspecified"))
      (node (ref "U7") (pin "28") (pinfunction "IO17_28") (pintype "unspecified"))
    )
    (net (code "43") (name "unconnected-(CN6-Pad6)") (class "Default")
      (node (ref "CN6") (pin "6") (pinfunction "6_6") (pintype "unspecified+no_connect"))
    )
    (net (code "44") (name "unconnected-(U1-SBU1-PadA8)") (class "Default")
      (node (ref "U1") (pin "A8") (pinfunction "SBU1_A8") (pintype "unspecified+no_connect"))
    )
    (net (code "45") (name "unconnected-(U1-SBU2-PadB8)") (class "Default")
      (node (ref "U1") (pin "B8") (pinfunction "SBU2_B8") (pintype "unspecified+no_connect"))
    )
    (net (code "46") (name "unconnected-(U2-DCP-Pad2)") (class "Default")
      (node (ref "U2") (pin "2") (pinfunction "DCP_2") (pintype "unspecified+no_connect"))
    )
    (net (code "47") (name "unconnected-(U2-LED1-Pad4)") (class "Default")
      (node (ref "U2") (pin "4") (pinfunction "LED1_4") (pintype "unspecified+no_connect"))
    )
    (net (code "48") (name "unconnected-(U2-LED2-Pad5)") (class "Default")
      (node (ref "U2") (pin "5") (pinfunction "LED2_5") (pintype "unspecified+no_connect"))
    )
    (net (code "49") (name "unconnected-(U5-CTS#-Pad9)") (class "Default")
      (node (ref "U5") (pin "9") (pinfunction "CTS#_9") (pintype "unspecified+no_connect"))
    )
    (net (code "50") (name "unconnected-(U5-DCD#-Pad12)") (class "Default")
      (node (ref "U5") (pin "12") (pinfunction "DCD#_12") (pintype "unspecified+no_connect"))
    )
    (net (code "51") (name "unconnected-(U5-DSR#-Pad10)") (class "Default")
      (node (ref "U5") (pin "10") (pinfunction "DSR#_10") (pintype "unspecified+no_connect"))
    )
    (net (code "52") (name "unconnected-(U5-NC.-Pad7)") (class "Default")
      (node (ref "U5") (pin "7") (pinfunction "NC._7") (pintype "unspecified+no_connect"))
    )
    (net (code "53") (name "unconnected-(U5-NC.-Pad8)") (class "Default")
      (node (ref "U5") (pin "8") (pinfunction "NC._8") (pintype "unspecified+no_connect"))
    )
    (net (code "54") (name "unconnected-(U5-R232-Pad15)") (class "Default")
      (node (ref "U5") (pin "15") (pinfunction "R232_15") (pintype "unspecified+no_connect"))
    )
    (net (code "55") (name "unconnected-(U5-RI#-Pad11)") (class "Default")
      (node (ref "U5") (pin "11") (pinfunction "RI#_11") (pintype "unspecified+no_connect"))
    )
    (net (code "56") (name "unconnected-(U7-IO5-Pad29)") (class "Default")
      (node (ref "U7") (pin "29") (pinfunction "IO5_29") (pintype "unspecified+no_connect"))
    )
    (net (code "57") (name "unconnected-(U7-IO12-Pad14)") (class "Default")
      (node (ref "U7") (pin "14") (pinfunction "IO12_14") (pintype "unspecified+no_connect"))
    )
    (net (code "58") (name "unconnected-(U7-IO15-Pad23)") (class "Default")
      (node (ref "U7") (pin "23") (pinfunction "IO15_23") (pintype "unspecified+no_connect"))
    )
    (net (code "59") (name "unconnected-(U7-NC-Pad32)") (class "Default")
      (node (ref "U7") (pin "32") (pinfunction "NC_32") (pintype "unspecified+no_connect"))
    )
    (net (code "60") (name "usb5v") (class "Default")
      (node (ref "D1") (pin "1") (pinfunction "1_1") (pintype "unspecified"))
      (node (ref "R2") (pin "2") (pinfunction "2_2") (pintype "unspecified"))
      (node (ref "U1") (pin "A4B9") (pinfunction "VBUS_A4B9") (pintype "unspecified"))
      (node (ref "U1") (pin "B4A9") (pinfunction "VBUS_B4A9") (pintype "unspecified"))
      (node (ref "U2") (pin "1") (pinfunction "VIN_1") (pintype "unspecified"))
    )
    (net (code "61") (name "usbd+") (class "Default")
      (node (ref "D2") (pin "1") (pinfunction "1_1") (pintype "unspecified"))
      (node (ref "U1") (pin "A6") (pinfunction "DP1_A6") (pintype "unspecified"))
      (node (ref "U1") (pin "B6") (pinfunction "DP2_B6") (pintype "unspecified"))
      (node (ref "U5") (pin "5") (pinfunction "D+_5") (pintype "unspecified"))
    )
    (net (code "62") (name "usbd-") (class "Default")
      (node (ref "D3") (pin "1") (pinfunction "1_1") (pintype "unspecified"))
      (node (ref "U1") (pin "A7") (pinfunction "DN1_A7") (pintype "unspecified"))
      (node (ref "U1") (pin "B7") (pinfunction "DN2_B7") (pintype "unspecified"))
      (node (ref "U5") (pin "6") (pinfunction "D-_6") (pintype "unspecified"))
    )
    (net (code "63") (name "vbat") (class "Default")
      (node (ref "CN1") (pin "3") (pinfunction "3_3") (pintype "unspecified"))
      (node (ref "CN1") (pin "4") (pinfunction "4_4") (pintype "unspecified"))
      (node (ref "CN2") (pin "1") (pinfunction "1_1") (pintype "unspecified"))
      (node (ref "CN2") (pin "2") (pinfunction "2_2") (pintype "unspecified"))
      (node (ref "CN3") (pin "3") (pinfunction "3_3") (pintype "unspecified"))
      (node (ref "CN3") (pin "4") (pinfunction "4_4") (pintype "unspecified"))
      (node (ref "R15") (pin "2") (pinfunction "2_2") (pintype "input"))
    )
    (net (code "64") (name "vread") (class "Default")
      (node (ref "R15") (pin "1") (pinfunction "1_1") (pintype "input"))
      (node (ref "R16") (pin "2") (pinfunction "2_2") (pintype "input"))
      (node (ref "U7") (pin "8") (pinfunction "IO32_8") (pintype "unspecified"))
    )
  )
)
